# PDB_Protection_Prototype.net
KiCad netlist of a schematic drawn in EAGLE
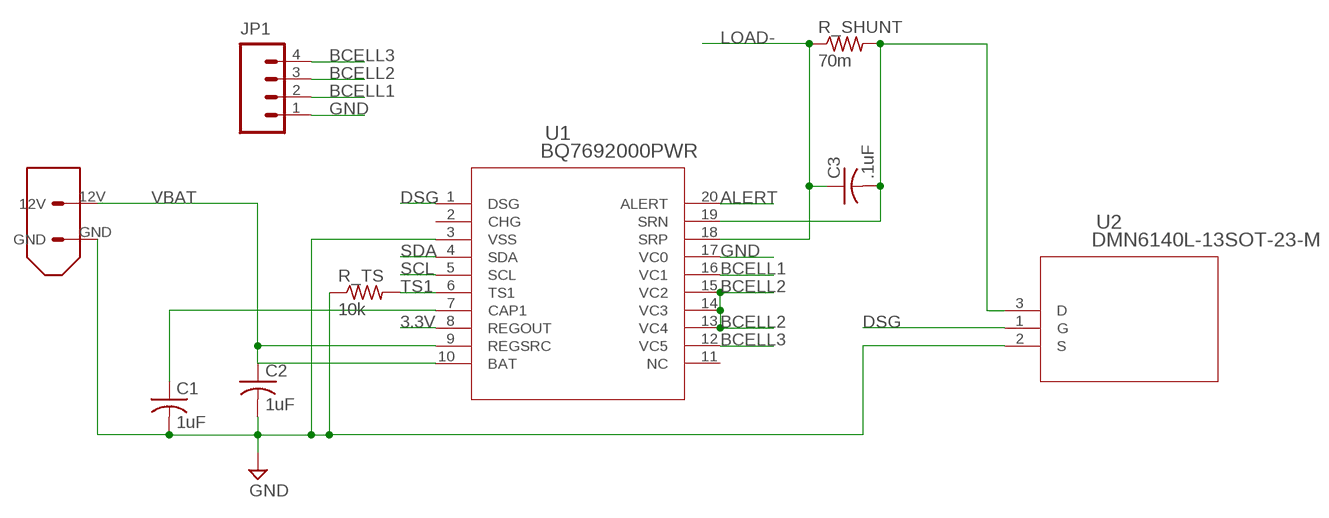
[diagram p0: schematic, sheet 1]

(export (version "E")
  (design (tool "Eeschema 10.0.6"))
  (components
    (comp (ref "C1")
      (value "1uF")
      (footprint "eagle-import:C0402")
      (fields (field (name "PART_NUMBER") "CGB2A1X5R1E105K033BC") (field (name "VOLTAGE") "25V"))
      (libsource (lib "eagle-import") (part "C-USC0402"))
    )
    (comp (ref "C2")
      (value "1uF")
      (footprint "eagle-import:C0402")
      (fields (field (name "PART_NUMBER") "CGB2A1X5R1E105K033BC") (field (name "VOLTAGE") "25V"))
      (libsource (lib "eagle-import") (part "C-USC0402"))
    )
    (comp (ref "C3")
      (value ".1uF")
      (footprint "eagle-import:C0402")
      (fields (field (name "PART_NUMBER") "CL05A104MP5NNNC") (field (name "VOLTAGE") "10V"))
      (libsource (lib "eagle-import") (part "C-USC0402"))
    )
    (comp (ref "JP1")
      (value "M041X04-MTA")
      (footprint "eagle-import:1X04-MTA")
      (libsource (lib "eagle-import") (part "M041X04-MTA"))
    )
    (comp (ref "R_SHUNT")
      (value "70m")
      (footprint "eagle-import:R2512")
      (fields
        (field (name "PART_NUMBER") "CRA2512-FZ-R070ELF")
        (field (name "POWER") "3W")
        (field (name "TOLERANCE") "1%")
      )
      (libsource (lib "eagle-import") (part "R-US_R2512"))
    )
    (comp (ref "R_TS")
      (value "10k")
      (footprint "eagle-import:R0603")
      (libsource (lib "eagle-import") (part "R-US_R0603"))
    )
    (comp (ref "U$1")
      (value "XT60CONNECTOR")
      (footprint "eagle-import:XT60CONNECTOR")
      (fields (field (name "PARTNUMBER") "PRT-10474 "))
      (libsource (lib "eagle-import") (part "XT60CONNECTOR"))
    )
    (comp (ref "U1")
      (value "BQ7692000PWR")
      (footprint "eagle-import:PW20")
      (libsource (lib "eagle-import") (part "BQ7692000PWR"))
    )
    (comp (ref "U2")
      (value "DMN6140L-13SOT-23-M")
      (footprint "eagle-import:SOT-23-M")
      (fields (field (name "MANUFACTURER_PART_NUMBER") "DMN6140L13"))
      (libsource (lib "eagle-import") (part "DMN6140L-13SOT-23-M"))
    )
  )
  (nets
    (net (code "1") (name "/3.3V") (class "Default")
      (node (ref "U1") (pin "8") (pinfunction "REGOUT_8") (pintype "power_in"))
    )
    (net (code "2") (name "/ALERT") (class "Default")
      (node (ref "U1") (pin "20") (pinfunction "ALERT_20") (pintype "bidirectional"))
    )
    (net (code "3") (name "/BCELL1") (class "Default")
      (node (ref "JP1") (pin "2") (pinfunction "2_2") (pintype "passive"))
      (node (ref "U1") (pin "16") (pinfunction "VC1_16") (pintype "input"))
    )
    (net (code "4") (name "/BCELL2") (class "Default")
      (node (ref "JP1") (pin "3") (pinfunction "3_3") (pintype "passive"))
      (node (ref "U1") (pin "13") (pinfunction "VC4_13") (pintype "input"))
      (node (ref "U1") (pin "14") (pinfunction "VC3_14") (pintype "input"))
      (node (ref "U1") (pin "15") (pinfunction "VC2_15") (pintype "input"))
    )
    (net (code "5") (name "/BCELL3") (class "Default")
      (node (ref "JP1") (pin "4") (pinfunction "4_4") (pintype "passive"))
      (node (ref "U1") (pin "12") (pinfunction "VC5_12") (pintype "input"))
    )
    (net (code "6") (name "/DSG") (class "Default")
      (node (ref "U1") (pin "1") (pinfunction "DSG_1") (pintype "output"))
      (node (ref "U2") (pin "1") (pinfunction "G_1") (pintype "passive"))
    )
    (net (code "7") (name "/LOAD-") (class "Default")
      (node (ref "C3") (pin "1") (pinfunction "1_1") (pintype "passive"))
      (node (ref "R_SHUNT") (pin "1") (pinfunction "1_1") (pintype "passive"))
      (node (ref "U1") (pin "18") (pinfunction "SRP_18") (pintype "input"))
    )
    (net (code "8") (name "/SCL") (class "Default")
      (node (ref "U1") (pin "5") (pinfunction "SCL_5") (pintype "input"))
    )
    (net (code "9") (name "/SDA") (class "Default")
      (node (ref "U1") (pin "4") (pinfunction "SDA_4") (pintype "bidirectional"))
    )
    (net (code "10") (name "/TS1") (class "Default")
      (node (ref "R_TS") (pin "2") (pinfunction "2_2") (pintype "passive"))
      (node (ref "U1") (pin "6") (pinfunction "TS1_6") (pintype "input"))
    )
    (net (code "11") (name "/VBAT") (class "Default")
      (node (ref "C2") (pin "1") (pinfunction "1_1") (pintype "passive"))
      (node (ref "U$1") (pin "12V") (pinfunction "12V_12V") (pintype "bidirectional"))
      (node (ref "U1") (pin "10") (pinfunction "BAT_10") (pintype "power_in"))
      (node (ref "U1") (pin "9") (pinfunction "REGSRC_9") (pintype "input"))
    )
    (net (code "12") (name "GND") (class "Default")
      (node (ref "C1") (pin "2") (pinfunction "2_2") (pintype "passive"))
      (node (ref "C2") (pin "2") (pinfunction "2_2") (pintype "passive"))
      (node (ref "JP1") (pin "1") (pinfunction "1_1") (pintype "passive"))
      (node (ref "R_TS") (pin "1") (pinfunction "1_1") (pintype "passive"))
      (node (ref "U$1") (pin "GND") (pinfunction "GND_GND") (pintype "bidirectional"))
      (node (ref "U1") (pin "17") (pinfunction "VC0_17") (pintype "input"))
      (node (ref "U1") (pin "3") (pinfunction "VSS_3") (pintype "power_in"))
      (node (ref "U2") (pin "2") (pinfunction "S_2") (pintype "passive"))
    )
    (net (code "13") (name "Net-(U1-CAP1)") (class "Default")
      (node (ref "C1") (pin "1") (pinfunction "1_1") (pintype "passive"))
      (node (ref "U1") (pin "7") (pinfunction "CAP1_7") (pintype "output"))
    )
    (net (code "14") (name "Net-(U1-SRN)") (class "Default")
      (node (ref "C3") (pin "2") (pinfunction "2_2") (pintype "passive"))
      (node (ref "R_SHUNT") (pin "2") (pinfunction "2_2") (pintype "passive"))
      (node (ref "U1") (pin "19") (pinfunction "SRN_19") (pintype "input"))
      (node (ref "U2") (pin "3") (pinfunction "D_3") (pintype "passive"))
    )
    (net (code "15") (name "unconnected-(U1-CHG-Pad2)") (class "Default")
      (node (ref "U1") (pin "2") (pinfunction "CHG_2") (pintype "output"))
    )
    (net (code "16") (name "unconnected-(U1-NC-Pad11)") (class "Default")
      (node (ref "U1") (pin "11") (pinfunction "NC_11") (pintype "no_connect"))
    )
  )
)
